# CAN_module.net
KiCad netlist of a schematic drawn in Altium Designer
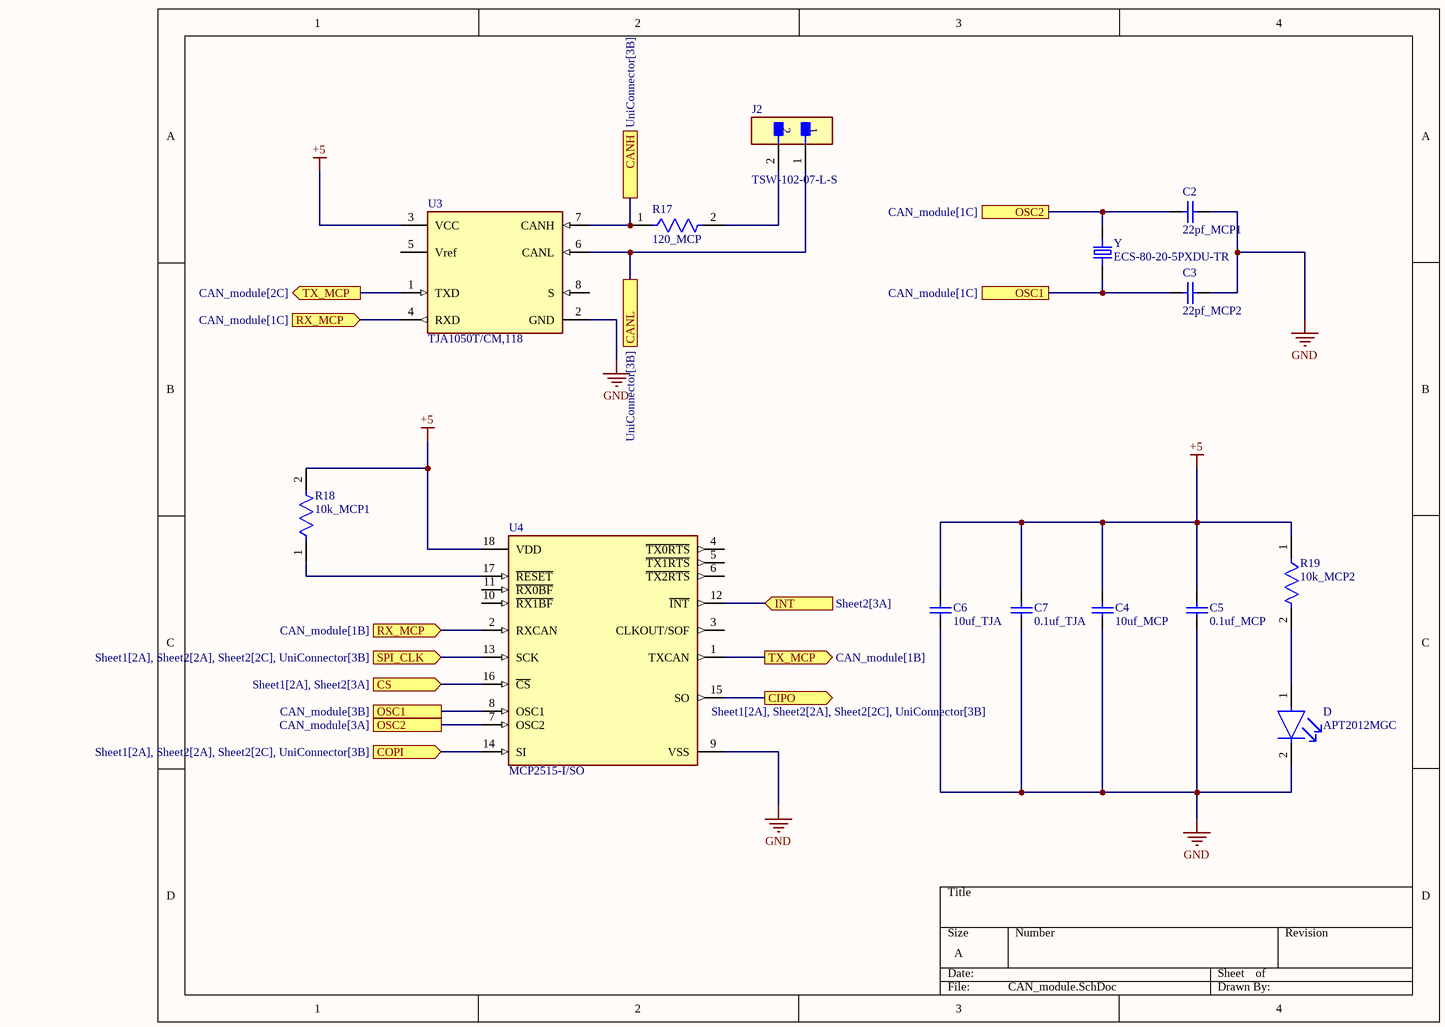
[diagram p0: CAN_module.SchDoc]

(export (version "E")
  (design (tool "Eeschema 10.0.6"))
  (components
    (comp (ref "C2")
      (value "22pf_MCP1")
      (footprint "CAPC2013X145X50NL20T20")
      (fields (field (name "MANUFACTURER") "Vitramon") (field (name "PART NUMBER") "VJ0805A220GXXCW1BC"))
      (libsource (lib "Altium Content Vault") (part "CAP"))
    )
    (comp (ref "C3")
      (value "22pf_MCP2")
      (footprint "CAPC2013X145X50NL20T20")
      (fields (field (name "MANUFACTURER") "Vitramon") (field (name "PART NUMBER") "VJ0805A220GXXCW1BC"))
      (libsource (lib "Altium Content Vault") (part "CAP"))
    )
    (comp (ref "C4")
      (value "10uf_MCP")
      (footprint "CAPC2013X145X50NL20T20")
      (fields (field (name "MANUFACTURER") "Vitramon") (field (name "PART NUMBER") "VJ0805A220GXXCW1BC"))
      (libsource (lib "Altium Content Vault") (part "CAP"))
    )
    (comp (ref "C5")
      (value "0.1uf_MCP")
      (footprint "CAPC2013X145X50NL20T20")
      (fields (field (name "MANUFACTURER") "Vitramon") (field (name "PART NUMBER") "VJ0805A220GXXCW1BC"))
      (libsource (lib "Altium Content Vault") (part "CAP"))
    )
    (comp (ref "C6")
      (value "10uf_TJA")
      (footprint "CAPC2013X145X50NL20T20")
      (fields (field (name "MANUFACTURER") "Vitramon") (field (name "PART NUMBER") "VJ0805A220GXXCW1BC"))
      (libsource (lib "Altium Content Vault") (part "CAP"))
    )
    (comp (ref "C7")
      (value "0.1uf_TJA")
      (footprint "CAPC2013X145X50NL20T20")
      (fields (field (name "MANUFACTURER") "Vitramon") (field (name "PART NUMBER") "VJ0805A220GXXCW1BC"))
      (libsource (lib "Altium Content Vault") (part "CAP"))
    )
    (comp (ref "D")
      (value "APT2012MGC")
      (footprint "FP-APT2012MGC-MFG")
      (description "LED GREEN CLEAR CHIP SMD")
      (libsource (lib "Altium Content Vault") (part "ab1c01a81903e929fc6c44469aada92"))
    )
    (comp (ref "J2")
      (value "TSW-102-07-L-S")
      (footprint "FP-TSW-102-07-L-S-MFG")
      (description "CONN HEADER VERT 2POS 2.54MM")
      (libsource (lib "Altium Content Vault") (part "3bc925449376181038e59eaffc5286c"))
    )
    (comp (ref "R17")
      (value "120_MCP")
      (footprint "FP-CRCW0805-e3-IPC_C")
      (description "RES Thick Film, 4.02Ω, 1%, 0.125W, 200ppm/°C, 0805")
      (fields (field (name "TOLERANCE") "1%"))
      (libsource (lib "Altium Content Vault") (part "1029c3af85768c4190bb7ad29bc67b5"))
    )
    (comp (ref "R18")
      (value "10k_MCP1")
      (footprint "FP-CRCW0805-e3-IPC_C")
      (description "RES Thick Film, 4.02Ω, 1%, 0.125W, 200ppm/°C, 0805")
      (fields (field (name "TOLERANCE") "1%"))
      (libsource (lib "Altium Content Vault") (part "1029c3af85768c4190bb7ad29bc67b5"))
    )
    (comp (ref "R19")
      (value "10k_MCP2")
      (footprint "FP-CRCW0805-e3-IPC_C")
      (description "RES Thick Film, 4.02Ω, 1%, 0.125W, 200ppm/°C, 0805")
      (fields (field (name "TOLERANCE") "1%"))
      (libsource (lib "Altium Content Vault") (part "1029c3af85768c4190bb7ad29bc67b5"))
    )
    (comp (ref "U3")
      (value "TJA1050T/CM,118")
      (footprint "FP-SOT96-1-IPC_A")
      (description "IC TRANSCEIVER HALF 1/1 8SO")
      (libsource (lib "Altium Content Vault") (part "cfdefafd38a55dc0607790f57b8a78f"))
    )
    (comp (ref "U4")
      (value "MCP2515-I/SO")
      (footprint "FP-C04-051-MFG")
      (description "IC CAN CONTROLLER W/SPI 18SOIC")
      (fields
        (field (name "MANUFACTURER") "Microchip")
        (field (name "OCTOPART") "https://octopart.com/mcp2515-i%2Fso-microchip-430187")
      )
      (libsource (lib "Altium Content Vault") (part "1c78ea6ff576bac94664e2637e1b479"))
    )
    (comp (ref "Y")
      (value "ECS-80-20-5PXDU-TR")
      (footprint "XTAL_ECS-80-20-5PXDU-TR")
      (description "8MHz Â±30ppm Crystal 20pF 60 Ohms HC-49/US")
      (fields (field (name "MF") "ECS Inc."))
      (libsource (lib "SnapEDAsch") (part "ECS-80-20-5PXDU-TR"))
    )
  )
  (nets
    (net (code "1") (name "+5") (class "Default")
      (node (ref "C4") (pin "2") (pinfunction "2_2") (pintype "passive"))
      (node (ref "C5") (pin "2") (pinfunction "2_2") (pintype "passive"))
      (node (ref "C6") (pin "2") (pinfunction "2_2") (pintype "passive"))
      (node (ref "C7") (pin "2") (pinfunction "2_2") (pintype "passive"))
      (node (ref "R18") (pin "2") (pinfunction "2_2") (pintype "passive"))
      (node (ref "R19") (pin "1") (pinfunction "1_1") (pintype "passive"))
      (node (ref "U3") (pin "3") (pinfunction "VCC_3") (pintype "power_in"))
      (node (ref "U4") (pin "18") (pinfunction "VDD_18") (pintype "power_in"))
    )
    (net (code "2") (name "/CANH") (class "Default")
      (node (ref "R17") (pin "1") (pinfunction "1_1") (pintype "passive"))
      (node (ref "U3") (pin "7") (pinfunction "CANH_7") (pintype "input"))
    )
    (net (code "3") (name "/CANL") (class "Default")
      (node (ref "J2") (pin "1") (pinfunction "1_1") (pintype "passive"))
      (node (ref "U3") (pin "6") (pinfunction "CANL_6") (pintype "input"))
    )
    (net (code "4") (name "/CIPO") (class "Default")
      (node (ref "U4") (pin "15") (pinfunction "SO_15") (pintype "output"))
    )
    (net (code "5") (name "/COPI") (class "Default")
      (node (ref "U4") (pin "14") (pinfunction "SI_14") (pintype "input"))
    )
    (net (code "6") (name "/CS") (class "Default")
      (node (ref "U4") (pin "16") (pinfunction "~{CS}_16") (pintype "input"))
    )
    (net (code "7") (name "/INT") (class "Default")
      (node (ref "U4") (pin "12") (pinfunction "~{INT}_12") (pintype "output"))
    )
    (net (code "8") (name "/OSC1") (class "Default")
      (node (ref "C3") (pin "1") (pinfunction "1_1") (pintype "passive"))
      (node (ref "U4") (pin "8") (pinfunction "OSC1_8") (pintype "input"))
      (node (ref "Y") (pin "1") (pinfunction "1_1") (pintype "passive"))
    )
    (net (code "9") (name "/OSC2") (class "Default")
      (node (ref "C2") (pin "1") (pinfunction "1_1") (pintype "passive"))
      (node (ref "U4") (pin "7") (pinfunction "OSC2_7") (pintype "input"))
      (node (ref "Y") (pin "2") (pinfunction "2_2") (pintype "passive"))
    )
    (net (code "10") (name "/RX_MCP") (class "Default")
      (node (ref "U3") (pin "4") (pinfunction "RXD_4") (pintype "output"))
      (node (ref "U4") (pin "2") (pinfunction "RXCAN_2") (pintype "input"))
    )
    (net (code "11") (name "/SPI_CLK") (class "Default")
      (node (ref "U4") (pin "13") (pinfunction "SCK_13") (pintype "input"))
    )
    (net (code "12") (name "/TX_MCP") (class "Default")
      (node (ref "U3") (pin "1") (pinfunction "TXD_1") (pintype "input"))
      (node (ref "U4") (pin "1") (pinfunction "TXCAN_1") (pintype "output"))
    )
    (net (code "13") (name "GND") (class "Default")
      (node (ref "C2") (pin "2") (pinfunction "2_2") (pintype "passive"))
      (node (ref "C3") (pin "2") (pinfunction "2_2") (pintype "passive"))
      (node (ref "C4") (pin "1") (pinfunction "1_1") (pintype "passive"))
      (node (ref "C5") (pin "1") (pinfunction "1_1") (pintype "passive"))
      (node (ref "C6") (pin "1") (pinfunction "1_1") (pintype "passive"))
      (node (ref "C7") (pin "1") (pinfunction "1_1") (pintype "passive"))
      (node (ref "D") (pin "2") (pinfunction "C_2") (pintype "passive"))
      (node (ref "U3") (pin "2") (pinfunction "GND_2") (pintype "power_in"))
      (node (ref "U4") (pin "9") (pinfunction "VSS_9") (pintype "power_in"))
    )
    (net (code "14") (name "Net-(D-A)") (class "Default")
      (node (ref "D") (pin "1") (pinfunction "A_1") (pintype "passive"))
      (node (ref "R19") (pin "2") (pinfunction "2_2") (pintype "passive"))
    )
    (net (code "15") (name "Net-(J2-Pad2)") (class "Default")
      (node (ref "J2") (pin "2") (pinfunction "2_2") (pintype "passive"))
      (node (ref "R17") (pin "2") (pinfunction "2_2") (pintype "passive"))
    )
    (net (code "16") (name "Net-(U4-~{RESET})") (class "Default")
      (node (ref "R18") (pin "1") (pinfunction "1_1") (pintype "passive"))
      (node (ref "U4") (pin "17") (pinfunction "~{RESET}_17") (pintype "input"))
    )
    (net (code "17") (name "unconnected-(U3-S-Pad8)") (class "Default")
      (node (ref "U3") (pin "8") (pinfunction "S_8") (pintype "input"))
    )
    (net (code "18") (name "unconnected-(U3-Vref-Pad5)") (class "Default")
      (node (ref "U3") (pin "5") (pinfunction "Vref_5") (pintype "power_in"))
    )
    (net (code "19") (name "unconnected-(U4-CLKOUT{slash}SOF-Pad3)") (class "Default")
      (node (ref "U4") (pin "3") (pinfunction "CLKOUT/SOF_3") (pintype "output"))
    )
    (net (code "20") (name "unconnected-(U4-~{RX0BF}-Pad11)") (class "Default")
      (node (ref "U4") (pin "11") (pinfunction "~{RX0BF}_11") (pintype "input"))
    )
    (net (code "21") (name "unconnected-(U4-~{RX1BF}-Pad10)") (class "Default")
      (node (ref "U4") (pin "10") (pinfunction "~{RX1BF}_10") (pintype "input"))
    )
    (net (code "22") (name "unconnected-(U4-~{TX0RTS}-Pad4)") (class "Default")
      (node (ref "U4") (pin "4") (pinfunction "~{TX0RTS}_4") (pintype "output"))
    )
    (net (code "23") (name "unconnected-(U4-~{TX1RTS}-Pad5)") (class "Default")
      (node (ref "U4") (pin "5") (pinfunction "~{TX1RTS}_5") (pintype "output"))
    )
    (net (code "24") (name "unconnected-(U4-~{TX2RTS}-Pad6)") (class "Default")
      (node (ref "U4") (pin "6") (pinfunction "~{TX2RTS}_6") (pintype "output"))
    )
  )
)
